# rev1_6.net
KiCad netlist of a schematic drawn in EAGLE
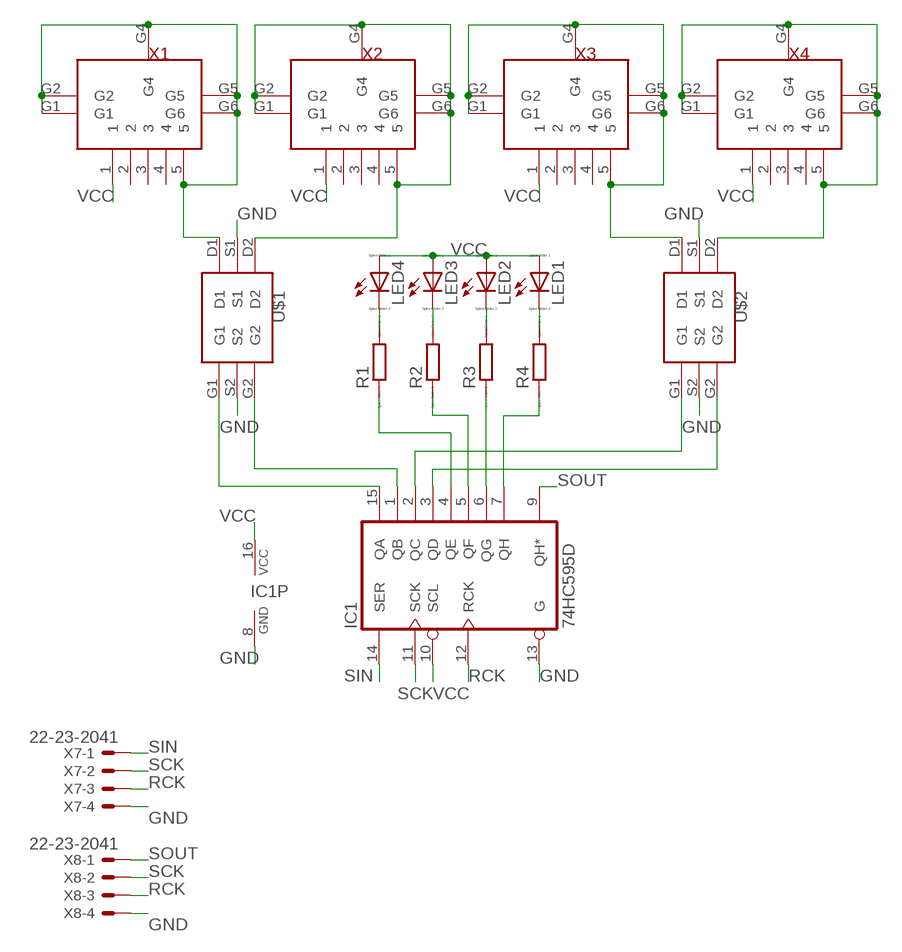
[diagram p0: schematic, sheet 1]

(export (version "E")
  (design (tool "Eeschema 10.0.6"))
  (components
    (comp (ref "IC1")
      (value "74HC595D")
      (footprint "eagle-import:SO16")
      (libsource (lib "eagle-import") (part "74595DHC"))
    )
    (comp (ref "LED1")
      (value "LED_E")
      (footprint "eagle-import:LED_1206")
      (libsource (lib "eagle-import") (part "LED_E"))
    )
    (comp (ref "LED2")
      (value "LED_E")
      (footprint "eagle-import:LED_1206")
      (libsource (lib "eagle-import") (part "LED_E"))
    )
    (comp (ref "LED3")
      (value "LED_E")
      (footprint "eagle-import:LED_1206")
      (libsource (lib "eagle-import") (part "LED_E"))
    )
    (comp (ref "LED4")
      (value "LED_E")
      (footprint "eagle-import:LED_1206")
      (libsource (lib "eagle-import") (part "LED_E"))
    )
    (comp (ref "R1")
      (value "RR1005")
      (footprint "eagle-import:R1005")
      (libsource (lib "eagle-import") (part "RR1005"))
    )
    (comp (ref "R2")
      (value "RR1005")
      (footprint "eagle-import:R1005")
      (libsource (lib "eagle-import") (part "RR1005"))
    )
    (comp (ref "R3")
      (value "RR1005")
      (footprint "eagle-import:R1005")
      (libsource (lib "eagle-import") (part "RR1005"))
    )
    (comp (ref "R4")
      (value "RR1005")
      (footprint "eagle-import:R1005")
      (libsource (lib "eagle-import") (part "RR1005"))
    )
    (comp (ref "U$1")
      (value "FDC6305N")
      (footprint "eagle-import:FDC6305")
      (libsource (lib "eagle-import") (part "FDC6305N"))
    )
    (comp (ref "U$2")
      (value "FDC6305N")
      (footprint "eagle-import:FDC6305")
      (libsource (lib "eagle-import") (part "FDC6305N"))
    )
    (comp (ref "X1")
      (value "MUSBV")
      (footprint "eagle-import:MUSBV")
      (libsource (lib "eagle-import") (part "MUSBV"))
    )
    (comp (ref "X2")
      (value "MUSBV")
      (footprint "eagle-import:MUSBV")
      (libsource (lib "eagle-import") (part "MUSBV"))
    )
    (comp (ref "X3")
      (value "MUSBV")
      (footprint "eagle-import:MUSBV")
      (libsource (lib "eagle-import") (part "MUSBV"))
    )
    (comp (ref "X4")
      (value "MUSBV")
      (footprint "eagle-import:MUSBV")
      (libsource (lib "eagle-import") (part "MUSBV"))
    )
    (comp (ref "X7")
      (value "22-23-2041")
      (footprint "eagle-import:22-23-2041")
      (fields (field (name "MF") "MOLEX"))
      (libsource (lib "eagle-import") (part "22-23-2041"))
    )
    (comp (ref "X8")
      (value "22-23-2041")
      (footprint "eagle-import:22-23-2041")
      (fields (field (name "MF") "MOLEX"))
      (libsource (lib "eagle-import") (part "22-23-2041"))
    )
  )
  (nets
    (net (code "1") (name "/GND") (class "Default")
      (node (ref "IC1") (pin "13") (pinfunction "G_13") (pintype "input"))
      (node (ref "IC1") (pin "8") (pinfunction "GND_8") (pintype "power_in"))
      (node (ref "U$1") (pin "S1") (pinfunction "S1_S1") (pintype "bidirectional"))
      (node (ref "U$1") (pin "S2") (pinfunction "S2_S2") (pintype "bidirectional"))
      (node (ref "U$2") (pin "S1") (pinfunction "S1_S1") (pintype "bidirectional"))
      (node (ref "U$2") (pin "S2") (pinfunction "S2_S2") (pintype "bidirectional"))
      (node (ref "X7") (pin "4") (pinfunction "S_4") (pintype "passive"))
      (node (ref "X8") (pin "4") (pinfunction "S_4") (pintype "passive"))
    )
    (net (code "2") (name "/RCK") (class "Default")
      (node (ref "IC1") (pin "12") (pinfunction "RCK_12") (pintype "input"))
      (node (ref "X7") (pin "3") (pinfunction "S_3") (pintype "passive"))
      (node (ref "X8") (pin "3") (pinfunction "S_3") (pintype "passive"))
    )
    (net (code "3") (name "/SCK") (class "Default")
      (node (ref "IC1") (pin "11") (pinfunction "SCK_11") (pintype "input"))
      (node (ref "X7") (pin "2") (pinfunction "S_2") (pintype "passive"))
      (node (ref "X8") (pin "2") (pinfunction "S_2") (pintype "passive"))
    )
    (net (code "4") (name "/SIN") (class "Default")
      (node (ref "IC1") (pin "14") (pinfunction "SER_14") (pintype "input"))
      (node (ref "X7") (pin "1") (pinfunction "S_1") (pintype "passive"))
    )
    (net (code "5") (name "/SOUT") (class "Default")
      (node (ref "IC1") (pin "9") (pinfunction "QH*_9") (pintype "tri_state"))
      (node (ref "X8") (pin "1") (pinfunction "S_1") (pintype "passive"))
    )
    (net (code "6") (name "/VCC") (class "Default")
      (node (ref "IC1") (pin "10") (pinfunction "SCL_10") (pintype "input"))
      (node (ref "IC1") (pin "16") (pinfunction "VCC_16") (pintype "power_in"))
      (node (ref "LED1") (pin "A") (pinfunction "A_A") (pintype "passive"))
      (node (ref "LED2") (pin "A") (pinfunction "A_A") (pintype "passive"))
      (node (ref "LED3") (pin "A") (pinfunction "A_A") (pintype "passive"))
      (node (ref "LED4") (pin "A") (pinfunction "A_A") (pintype "passive"))
      (node (ref "X1") (pin "1") (pinfunction "1_1") (pintype "bidirectional"))
      (node (ref "X2") (pin "1") (pinfunction "1_1") (pintype "bidirectional"))
      (node (ref "X3") (pin "1") (pinfunction "1_1") (pintype "bidirectional"))
      (node (ref "X4") (pin "1") (pinfunction "1_1") (pintype "bidirectional"))
    )
    (net (code "7") (name "Net-(IC1A-QA)") (class "Default")
      (node (ref "IC1") (pin "15") (pinfunction "QA_15") (pintype "tri_state"))
      (node (ref "U$1") (pin "G1") (pinfunction "G1_G1") (pintype "bidirectional"))
    )
    (net (code "8") (name "Net-(IC1A-QB)") (class "Default")
      (node (ref "IC1") (pin "1") (pinfunction "QB_1") (pintype "tri_state"))
      (node (ref "U$1") (pin "G2") (pinfunction "G2_G2") (pintype "bidirectional"))
    )
    (net (code "9") (name "Net-(IC1A-QC)") (class "Default")
      (node (ref "IC1") (pin "2") (pinfunction "QC_2") (pintype "tri_state"))
      (node (ref "U$2") (pin "G1") (pinfunction "G1_G1") (pintype "bidirectional"))
    )
    (net (code "10") (name "Net-(IC1A-QD)") (class "Default")
      (node (ref "IC1") (pin "3") (pinfunction "QD_3") (pintype "tri_state"))
      (node (ref "U$2") (pin "G2") (pinfunction "G2_G2") (pintype "bidirectional"))
    )
    (net (code "11") (name "Net-(IC1A-QE)") (class "Default")
      (node (ref "IC1") (pin "4") (pinfunction "QE_4") (pintype "tri_state"))
      (node (ref "R1") (pin "1") (pinfunction "1_1") (pintype "passive"))
    )
    (net (code "12") (name "Net-(IC1A-QF)") (class "Default")
      (node (ref "IC1") (pin "5") (pinfunction "QF_5") (pintype "tri_state"))
      (node (ref "R2") (pin "1") (pinfunction "1_1") (pintype "passive"))
    )
    (net (code "13") (name "Net-(IC1A-QG)") (class "Default")
      (node (ref "IC1") (pin "6") (pinfunction "QG_6") (pintype "tri_state"))
      (node (ref "R3") (pin "1") (pinfunction "1_1") (pintype "passive"))
    )
    (net (code "14") (name "Net-(IC1A-QH)") (class "Default")
      (node (ref "IC1") (pin "7") (pinfunction "QH_7") (pintype "tri_state"))
      (node (ref "R4") (pin "1") (pinfunction "1_1") (pintype "passive"))
    )
    (net (code "15") (name "Net-(LED1-PadC)") (class "Default")
      (node (ref "LED1") (pin "C") (pinfunction "C_C") (pintype "passive"))
      (node (ref "R4") (pin "2") (pinfunction "2_2") (pintype "passive"))
    )
    (net (code "16") (name "Net-(LED2-PadC)") (class "Default")
      (node (ref "LED2") (pin "C") (pinfunction "C_C") (pintype "passive"))
      (node (ref "R3") (pin "2") (pinfunction "2_2") (pintype "passive"))
    )
    (net (code "17") (name "Net-(LED3-PadC)") (class "Default")
      (node (ref "LED3") (pin "C") (pinfunction "C_C") (pintype "passive"))
      (node (ref "R2") (pin "2") (pinfunction "2_2") (pintype "passive"))
    )
    (net (code "18") (name "Net-(LED4-PadC)") (class "Default")
      (node (ref "LED4") (pin "C") (pinfunction "C_C") (pintype "passive"))
      (node (ref "R1") (pin "2") (pinfunction "2_2") (pintype "passive"))
    )
    (net (code "19") (name "Net-(U$1-PadD1)") (class "Default")
      (node (ref "U$1") (pin "D1") (pinfunction "D1_D1") (pintype "bidirectional"))
      (node (ref "X1") (pin "5") (pinfunction "5_5") (pintype "bidirectional"))
      (node (ref "X1") (pin "G1") (pinfunction "G1_G1") (pintype "bidirectional"))
      (node (ref "X1") (pin "G2") (pinfunction "G2_G2") (pintype "bidirectional"))
      (node (ref "X1") (pin "G4") (pinfunction "G4_G4") (pintype "bidirectional"))
      (node (ref "X1") (pin "G5") (pinfunction "G5_G5") (pintype "bidirectional"))
      (node (ref "X1") (pin "G6") (pinfunction "G6_G6") (pintype "bidirectional"))
    )
    (net (code "20") (name "Net-(U$1-PadD2)") (class "Default")
      (node (ref "U$1") (pin "D2") (pinfunction "D2_D2") (pintype "bidirectional"))
      (node (ref "X2") (pin "5") (pinfunction "5_5") (pintype "bidirectional"))
      (node (ref "X2") (pin "G1") (pinfunction "G1_G1") (pintype "bidirectional"))
      (node (ref "X2") (pin "G2") (pinfunction "G2_G2") (pintype "bidirectional"))
      (node (ref "X2") (pin "G4") (pinfunction "G4_G4") (pintype "bidirectional"))
      (node (ref "X2") (pin "G5") (pinfunction "G5_G5") (pintype "bidirectional"))
      (node (ref "X2") (pin "G6") (pinfunction "G6_G6") (pintype "bidirectional"))
    )
    (net (code "21") (name "Net-(U$2-PadD1)") (class "Default")
      (node (ref "U$2") (pin "D1") (pinfunction "D1_D1") (pintype "bidirectional"))
      (node (ref "X3") (pin "5") (pinfunction "5_5") (pintype "bidirectional"))
      (node (ref "X3") (pin "G1") (pinfunction "G1_G1") (pintype "bidirectional"))
      (node (ref "X3") (pin "G2") (pinfunction "G2_G2") (pintype "bidirectional"))
      (node (ref "X3") (pin "G4") (pinfunction "G4_G4") (pintype "bidirectional"))
      (node (ref "X3") (pin "G5") (pinfunction "G5_G5") (pintype "bidirectional"))
      (node (ref "X3") (pin "G6") (pinfunction "G6_G6") (pintype "bidirectional"))
    )
    (net (code "22") (name "Net-(U$2-PadD2)") (class "Default")
      (node (ref "U$2") (pin "D2") (pinfunction "D2_D2") (pintype "bidirectional"))
      (node (ref "X4") (pin "5") (pinfunction "5_5") (pintype "bidirectional"))
      (node (ref "X4") (pin "G1") (pinfunction "G1_G1") (pintype "bidirectional"))
      (node (ref "X4") (pin "G2") (pinfunction "G2_G2") (pintype "bidirectional"))
      (node (ref "X4") (pin "G4") (pinfunction "G4_G4") (pintype "bidirectional"))
      (node (ref "X4") (pin "G5") (pinfunction "G5_G5") (pintype "bidirectional"))
      (node (ref "X4") (pin "G6") (pinfunction "G6_G6") (pintype "bidirectional"))
    )
    (net (code "23") (name "unconnected-(X1-Pad2)") (class "Default")
      (node (ref "X1") (pin "2") (pinfunction "2_2") (pintype "bidirectional"))
    )
    (net (code "24") (name "unconnected-(X1-Pad3)") (class "Default")
      (node (ref "X1") (pin "3") (pinfunction "3_3") (pintype "bidirectional"))
    )
    (net (code "25") (name "unconnected-(X1-Pad4)") (class "Default")
      (node (ref "X1") (pin "4") (pinfunction "4_4") (pintype "bidirectional"))
    )
    (net (code "26") (name "unconnected-(X2-Pad2)") (class "Default")
      (node (ref "X2") (pin "2") (pinfunction "2_2") (pintype "bidirectional"))
    )
    (net (code "27") (name "unconnected-(X2-Pad3)") (class "Default")
      (node (ref "X2") (pin "3") (pinfunction "3_3") (pintype "bidirectional"))
    )
    (net (code "28") (name "unconnected-(X2-Pad4)") (class "Default")
      (node (ref "X2") (pin "4") (pinfunction "4_4") (pintype "bidirectional"))
    )
    (net (code "29") (name "unconnected-(X3-Pad2)") (class "Default")
      (node (ref "X3") (pin "2") (pinfunction "2_2") (pintype "bidirectional"))
    )
    (net (code "30") (name "unconnected-(X3-Pad3)") (class "Default")
      (node (ref "X3") (pin "3") (pinfunction "3_3") (pintype "bidirectional"))
    )
    (net (code "31") (name "unconnected-(X3-Pad4)") (class "Default")
      (node (ref "X3") (pin "4") (pinfunction "4_4") (pintype "bidirectional"))
    )
    (net (code "32") (name "unconnected-(X4-Pad2)") (class "Default")
      (node (ref "X4") (pin "2") (pinfunction "2_2") (pintype "bidirectional"))
    )
    (net (code "33") (name "unconnected-(X4-Pad3)") (class "Default")
      (node (ref "X4") (pin "3") (pinfunction "3_3") (pintype "bidirectional"))
    )
    (net (code "34") (name "unconnected-(X4-Pad4)") (class "Default")
      (node (ref "X4") (pin "4") (pinfunction "4_4") (pintype "bidirectional"))
    )
  )
)
